# Corsa_LCD.net
KiCad netlist of a schematic drawn in EAGLE
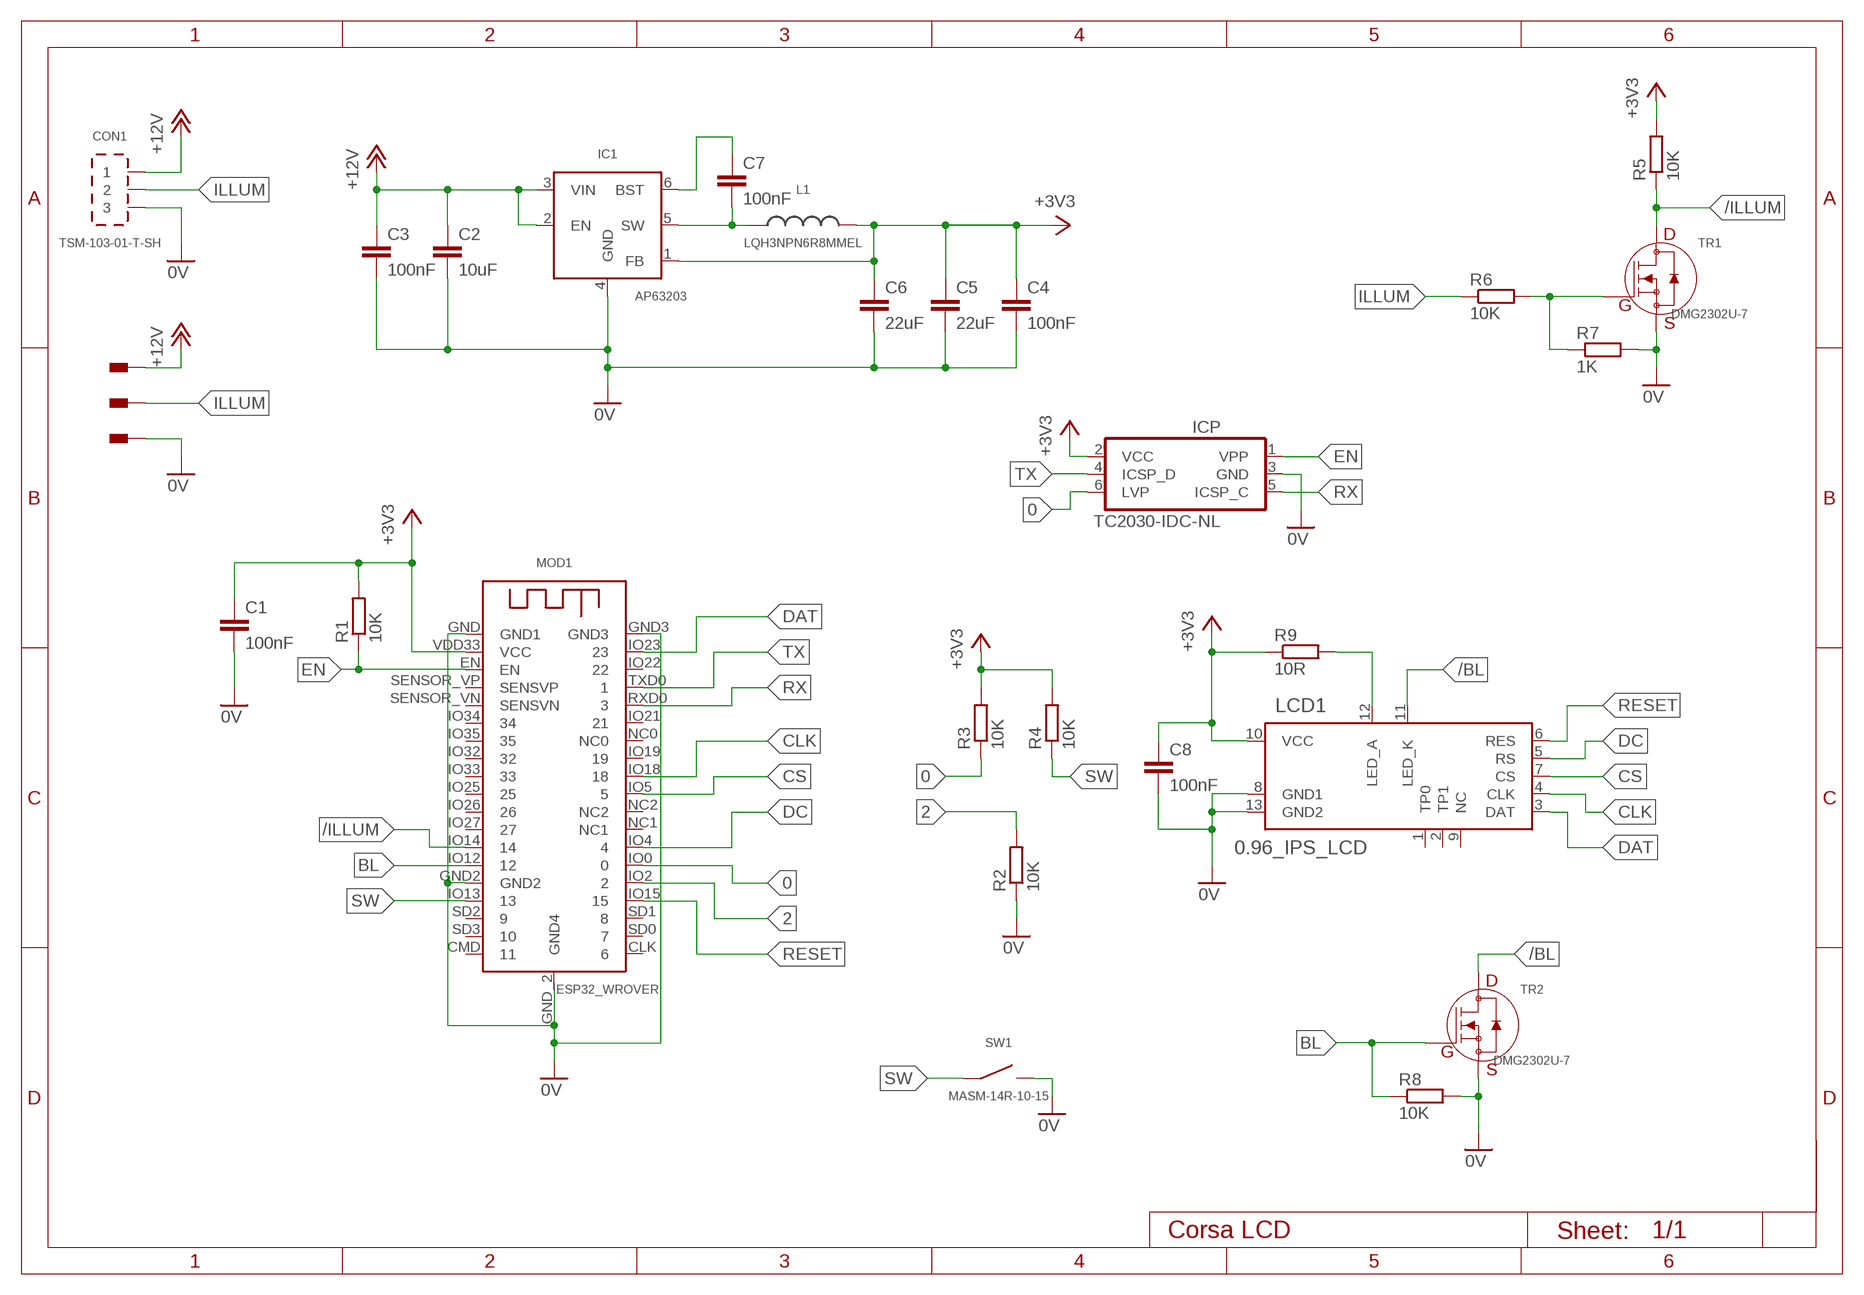
[diagram p0: schematic, sheet 1]

(export (version "E")
  (design (tool "Eeschema 10.0.6"))
  (components
    (comp (ref "C1")
      (value "100nF")
      (footprint "eagle-import:C0603")
      (libsource (lib "eagle-import") (part "C-EUC0603"))
    )
    (comp (ref "C2")
      (value "10uF")
      (footprint "eagle-import:C0603")
      (libsource (lib "eagle-import") (part "C-EUC0603"))
    )
    (comp (ref "C3")
      (value "100nF")
      (footprint "eagle-import:C0603")
      (libsource (lib "eagle-import") (part "C-EUC0603"))
    )
    (comp (ref "C4")
      (value "100nF")
      (footprint "eagle-import:C0603")
      (libsource (lib "eagle-import") (part "C-EUC0603"))
    )
    (comp (ref "C5")
      (value "22uF")
      (footprint "eagle-import:C0603")
      (libsource (lib "eagle-import") (part "C-EUC0603"))
    )
    (comp (ref "C6")
      (value "22uF")
      (footprint "eagle-import:C0603")
      (libsource (lib "eagle-import") (part "C-EUC0603"))
    )
    (comp (ref "C7")
      (value "100nF")
      (footprint "eagle-import:C0603")
      (libsource (lib "eagle-import") (part "C-EUC0603"))
    )
    (comp (ref "C8")
      (value "100nF")
      (footprint "eagle-import:C0603")
      (libsource (lib "eagle-import") (part "C-EUC0603"))
    )
    (comp (ref "CON1")
      (value "TSM-103-01-T-SH")
      (footprint "eagle-import:TSM-103-01-T-SH")
      (libsource (lib "eagle-import") (part "TSM-103-01-T-SH"))
    )
    (comp (ref "IC1")
      (value "AP63203")
      (footprint "eagle-import:TSOT26")
      (libsource (lib "eagle-import") (part "AP63203"))
    )
    (comp (ref "ICP")
      (value "TC2030-IDC-NL")
      (footprint "eagle-import:TC2030-IDC-NL")
      (libsource (lib "eagle-import") (part "TC2030-IDC-NL"))
    )
    (comp (ref "L1")
      (value "LQH3NPN6R8MMEL")
      (footprint "eagle-import:LQH3NPN")
      (libsource (lib "eagle-import") (part "LQH3NPN6R8MMEL"))
    )
    (comp (ref "LCD1")
      (value "0.96_IPS_LCD")
      (footprint "eagle-import:0.96_IPS_LCD")
      (libsource (lib "eagle-import") (part "0.96_IPS_LCD"))
    )
    (comp (ref "MOD1")
      (value "ESP32_WROVER")
      (footprint "eagle-import:ESP32_WROOVER")
      (libsource (lib "eagle-import") (part "ESP32_WROOVER"))
    )
    (comp (ref "PIN1")
      (value "SOLDERPAD")
      (footprint "eagle-import:SOLDERPAD")
      (libsource (lib "eagle-import") (part "SOLDERPAD"))
    )
    (comp (ref "PIN2")
      (value "SOLDERPAD")
      (footprint "eagle-import:SOLDERPAD")
      (libsource (lib "eagle-import") (part "SOLDERPAD"))
    )
    (comp (ref "PIN3")
      (value "SOLDERPAD")
      (footprint "eagle-import:SOLDERPAD")
      (libsource (lib "eagle-import") (part "SOLDERPAD"))
    )
    (comp (ref "R1")
      (value "10K")
      (footprint "eagle-import:R0603")
      (libsource (lib "eagle-import") (part "R-EU_R0603"))
    )
    (comp (ref "R2")
      (value "10K")
      (footprint "eagle-import:R0603")
      (libsource (lib "eagle-import") (part "R-EU_R0603"))
    )
    (comp (ref "R3")
      (value "10K")
      (footprint "eagle-import:R0603")
      (libsource (lib "eagle-import") (part "R-EU_R0603"))
    )
    (comp (ref "R4")
      (value "10K")
      (footprint "eagle-import:R0603")
      (libsource (lib "eagle-import") (part "R-EU_R0603"))
    )
    (comp (ref "R5")
      (value "10K")
      (footprint "eagle-import:R0603")
      (libsource (lib "eagle-import") (part "R-EU_R0603"))
    )
    (comp (ref "R6")
      (value "10K")
      (footprint "eagle-import:R0603")
      (libsource (lib "eagle-import") (part "R-EU_R0603"))
    )
    (comp (ref "R7")
      (value "1K")
      (footprint "eagle-import:R0603")
      (libsource (lib "eagle-import") (part "R-EU_R0603"))
    )
    (comp (ref "R8")
      (value "10K")
      (footprint "eagle-import:R0603")
      (libsource (lib "eagle-import") (part "R-EU_R0603"))
    )
    (comp (ref "R9")
      (value "10R")
      (footprint "eagle-import:R0603")
      (libsource (lib "eagle-import") (part "R-EU_R0603"))
    )
    (comp (ref "SW1")
      (value "MASM-14R-10-15")
      (footprint "eagle-import:MASM-14")
      (libsource (lib "eagle-import") (part "MASM-14R-10-15"))
    )
    (comp (ref "TR1")
      (value "DMG2302U-7")
      (footprint "eagle-import:SOT23")
      (libsource (lib "eagle-import") (part "DMG2302U-7"))
    )
    (comp (ref "TR2")
      (value "DMG2302U-7")
      (footprint "eagle-import:SOT23")
      (libsource (lib "eagle-import") (part "DMG2302U-7"))
    )
  )
  (nets
    (net (code "1") (name "+3V3") (class "Default")
      (node (ref "C1") (pin "1") (pinfunction "1_1") (pintype "passive"))
      (node (ref "C4") (pin "1") (pinfunction "1_1") (pintype "passive"))
      (node (ref "C5") (pin "1") (pinfunction "1_1") (pintype "passive"))
      (node (ref "C6") (pin "1") (pinfunction "1_1") (pintype "passive"))
      (node (ref "C8") (pin "1") (pinfunction "1_1") (pintype "passive"))
      (node (ref "IC1") (pin "1") (pinfunction "FB_1") (pintype "bidirectional"))
      (node (ref "ICP") (pin "2") (pinfunction "VCC_2") (pintype "passive"))
      (node (ref "L1") (pin "2") (pinfunction "2_2") (pintype "bidirectional"))
      (node (ref "LCD1") (pin "10") (pinfunction "VCC_10") (pintype "bidirectional"))
      (node (ref "MOD1") (pin "VDD33") (pinfunction "VCC_VDD33") (pintype "bidirectional"))
      (node (ref "R1") (pin "2") (pinfunction "2_2") (pintype "passive"))
      (node (ref "R3") (pin "2") (pinfunction "2_2") (pintype "passive"))
      (node (ref "R4") (pin "2") (pinfunction "2_2") (pintype "passive"))
      (node (ref "R5") (pin "2") (pinfunction "2_2") (pintype "passive"))
      (node (ref "R9") (pin "1") (pinfunction "1_1") (pintype "passive"))
    )
    (net (code "2") (name "+12V") (class "Default")
      (node (ref "C2") (pin "1") (pinfunction "1_1") (pintype "passive"))
      (node (ref "C3") (pin "1") (pinfunction "1_1") (pintype "passive"))
      (node (ref "CON1") (pin "1") (pinfunction "1_1") (pintype "bidirectional"))
      (node (ref "IC1") (pin "2") (pinfunction "EN_2") (pintype "bidirectional"))
      (node (ref "IC1") (pin "3") (pinfunction "VIN_3") (pintype "bidirectional"))
      (node (ref "PIN1") (pin "1") (pinfunction "1_1") (pintype "bidirectional"))
    )
    (net (code "3") (name "0") (class "Default")
      (node (ref "ICP") (pin "6") (pinfunction "LVP_6") (pintype "passive"))
      (node (ref "MOD1") (pin "IO0") (pinfunction "0_IO0") (pintype "bidirectional"))
      (node (ref "R3") (pin "1") (pinfunction "1_1") (pintype "passive"))
    )
    (net (code "4") (name "0V") (class "Default")
      (node (ref "C1") (pin "2") (pinfunction "2_2") (pintype "passive"))
      (node (ref "C2") (pin "2") (pinfunction "2_2") (pintype "passive"))
      (node (ref "C3") (pin "2") (pinfunction "2_2") (pintype "passive"))
      (node (ref "C4") (pin "2") (pinfunction "2_2") (pintype "passive"))
      (node (ref "C5") (pin "2") (pinfunction "2_2") (pintype "passive"))
      (node (ref "C6") (pin "2") (pinfunction "2_2") (pintype "passive"))
      (node (ref "C8") (pin "2") (pinfunction "2_2") (pintype "passive"))
      (node (ref "CON1") (pin "3") (pinfunction "3_3") (pintype "bidirectional"))
      (node (ref "IC1") (pin "4") (pinfunction "GND_4") (pintype "bidirectional"))
      (node (ref "ICP") (pin "3") (pinfunction "GND_3") (pintype "passive"))
      (node (ref "LCD1") (pin "13") (pinfunction "GND2_13") (pintype "bidirectional"))
      (node (ref "LCD1") (pin "8") (pinfunction "GND1_8") (pintype "bidirectional"))
      (node (ref "MOD1") (pin "GND") (pinfunction "GND1_GND") (pintype "bidirectional"))
      (node (ref "MOD1") (pin "GND2") (pinfunction "GND2_GND2") (pintype "bidirectional"))
      (node (ref "MOD1") (pin "GND3") (pinfunction "GND3_GND3") (pintype "bidirectional"))
      (node (ref "MOD1") (pin "GND_2") (pinfunction "GND4_GND_2") (pintype "bidirectional"))
      (node (ref "PIN3") (pin "1") (pinfunction "1_1") (pintype "bidirectional"))
      (node (ref "R2") (pin "1") (pinfunction "1_1") (pintype "passive"))
      (node (ref "R7") (pin "2") (pinfunction "2_2") (pintype "passive"))
      (node (ref "R8") (pin "2") (pinfunction "2_2") (pintype "passive"))
      (node (ref "SW1") (pin "2") (pinfunction "2_2") (pintype "bidirectional"))
      (node (ref "TR1") (pin "2") (pinfunction "S_2") (pintype "bidirectional"))
      (node (ref "TR2") (pin "2") (pinfunction "S_2") (pintype "bidirectional"))
    )
    (net (code "5") (name "2") (class "Default")
      (node (ref "MOD1") (pin "IO2") (pinfunction "2_IO2") (pintype "bidirectional"))
      (node (ref "R2") (pin "2") (pinfunction "2_2") (pintype "passive"))
    )
    (net (code "6") (name "BL") (class "Default")
      (node (ref "MOD1") (pin "IO12") (pinfunction "12_IO12") (pintype "bidirectional"))
      (node (ref "R8") (pin "1") (pinfunction "1_1") (pintype "passive"))
      (node (ref "TR2") (pin "1") (pinfunction "G_1") (pintype "bidirectional"))
    )
    (net (code "7") (name "CLK") (class "Default")
      (node (ref "LCD1") (pin "4") (pinfunction "CLK_4") (pintype "bidirectional"))
      (node (ref "MOD1") (pin "IO18") (pinfunction "18_IO18") (pintype "bidirectional"))
    )
    (net (code "8") (name "CS") (class "Default")
      (node (ref "LCD1") (pin "7") (pinfunction "CS_7") (pintype "bidirectional"))
      (node (ref "MOD1") (pin "IO5") (pinfunction "5_IO5") (pintype "bidirectional"))
    )
    (net (code "9") (name "DAT") (class "Default")
      (node (ref "LCD1") (pin "3") (pinfunction "DAT_3") (pintype "bidirectional"))
      (node (ref "MOD1") (pin "IO23") (pinfunction "23_IO23") (pintype "bidirectional"))
    )
    (net (code "10") (name "DC") (class "Default")
      (node (ref "LCD1") (pin "5") (pinfunction "RS_5") (pintype "bidirectional"))
      (node (ref "MOD1") (pin "IO4") (pinfunction "4_IO4") (pintype "bidirectional"))
    )
    (net (code "11") (name "EN") (class "Default")
      (node (ref "ICP") (pin "1") (pinfunction "VPP_1") (pintype "passive"))
      (node (ref "MOD1") (pin "EN") (pinfunction "EN_EN") (pintype "bidirectional"))
      (node (ref "R1") (pin "1") (pinfunction "1_1") (pintype "passive"))
    )
    (net (code "12") (name "ILLUM") (class "Default")
      (node (ref "CON1") (pin "2") (pinfunction "2_2") (pintype "bidirectional"))
      (node (ref "PIN2") (pin "1") (pinfunction "1_1") (pintype "bidirectional"))
      (node (ref "R6") (pin "1") (pinfunction "1_1") (pintype "passive"))
    )
    (net (code "13") (name "Net-(IC1-BST)") (class "Default")
      (node (ref "C7") (pin "1") (pinfunction "1_1") (pintype "passive"))
      (node (ref "IC1") (pin "6") (pinfunction "BST_6") (pintype "bidirectional"))
    )
    (net (code "14") (name "Net-(IC1-SW)") (class "Default")
      (node (ref "C7") (pin "2") (pinfunction "2_2") (pintype "passive"))
      (node (ref "IC1") (pin "5") (pinfunction "SW_5") (pintype "bidirectional"))
      (node (ref "L1") (pin "1") (pinfunction "1_1") (pintype "bidirectional"))
    )
    (net (code "15") (name "Net-(LCD1-LED_A)") (class "Default")
      (node (ref "LCD1") (pin "12") (pinfunction "LED_A_12") (pintype "bidirectional"))
      (node (ref "R9") (pin "2") (pinfunction "2_2") (pintype "passive"))
    )
    (net (code "16") (name "Net-(TR1-G)") (class "Default")
      (node (ref "R6") (pin "2") (pinfunction "2_2") (pintype "passive"))
      (node (ref "R7") (pin "1") (pinfunction "1_1") (pintype "passive"))
      (node (ref "TR1") (pin "1") (pinfunction "G_1") (pintype "bidirectional"))
    )
    (net (code "17") (name "RESET") (class "Default")
      (node (ref "LCD1") (pin "6") (pinfunction "RES_6") (pintype "bidirectional"))
      (node (ref "MOD1") (pin "IO15") (pinfunction "15_IO15") (pintype "bidirectional"))
    )
    (net (code "18") (name "RX") (class "Default")
      (node (ref "ICP") (pin "5") (pinfunction "ICSP_C_5") (pintype "passive"))
      (node (ref "MOD1") (pin "RXD0") (pinfunction "3_RXD0") (pintype "bidirectional"))
    )
    (net (code "19") (name "SW") (class "Default")
      (node (ref "MOD1") (pin "IO13") (pinfunction "13_IO13") (pintype "bidirectional"))
      (node (ref "R4") (pin "1") (pinfunction "1_1") (pintype "passive"))
      (node (ref "SW1") (pin "1") (pinfunction "1_1") (pintype "bidirectional"))
    )
    (net (code "20") (name "TX") (class "Default")
      (node (ref "ICP") (pin "4") (pinfunction "ICSP_D_4") (pintype "passive"))
      (node (ref "MOD1") (pin "TXD0") (pinfunction "1_TXD0") (pintype "bidirectional"))
    )
    (net (code "21") (name "unconnected-(LCD1-NC-Pad9)") (class "Default")
      (node (ref "LCD1") (pin "9") (pinfunction "NC_9") (pintype "bidirectional"))
    )
    (net (code "22") (name "unconnected-(LCD1-TP0-Pad1)") (class "Default")
      (node (ref "LCD1") (pin "1") (pinfunction "TP0_1") (pintype "bidirectional"))
    )
    (net (code "23") (name "unconnected-(LCD1-TP1-Pad2)") (class "Default")
      (node (ref "LCD1") (pin "2") (pinfunction "TP1_2") (pintype "bidirectional"))
    )
    (net (code "24") (name "unconnected-(MOD1-6-PadCLK)") (class "Default")
      (node (ref "MOD1") (pin "CLK") (pinfunction "6_CLK") (pintype "bidirectional"))
    )
    (net (code "25") (name "unconnected-(MOD1-7-PadSD0)") (class "Default")
      (node (ref "MOD1") (pin "SD0") (pinfunction "7_SD0") (pintype "bidirectional"))
    )
    (net (code "26") (name "unconnected-(MOD1-8-PadSD1)") (class "Default")
      (node (ref "MOD1") (pin "SD1") (pinfunction "8_SD1") (pintype "bidirectional"))
    )
    (net (code "27") (name "unconnected-(MOD1-9-PadSD2)") (class "Default")
      (node (ref "MOD1") (pin "SD2") (pinfunction "9_SD2") (pintype "bidirectional"))
    )
    (net (code "28") (name "unconnected-(MOD1-10-PadSD3)") (class "Default")
      (node (ref "MOD1") (pin "SD3") (pinfunction "10_SD3") (pintype "bidirectional"))
    )
    (net (code "29") (name "unconnected-(MOD1-11-PadCMD)") (class "Default")
      (node (ref "MOD1") (pin "CMD") (pinfunction "11_CMD") (pintype "bidirectional"))
    )
    (net (code "30") (name "unconnected-(MOD1-19-PadIO19)") (class "Default")
      (node (ref "MOD1") (pin "IO19") (pinfunction "19_IO19") (pintype "bidirectional"))
    )
    (net (code "31") (name "unconnected-(MOD1-21-PadIO21)") (class "Default")
      (node (ref "MOD1") (pin "IO21") (pinfunction "21_IO21") (pintype "bidirectional"))
    )
    (net (code "32") (name "unconnected-(MOD1-22-PadIO22)") (class "Default")
      (node (ref "MOD1") (pin "IO22") (pinfunction "22_IO22") (pintype "bidirectional"))
    )
    (net (code "33") (name "unconnected-(MOD1-25-PadIO25)") (class "Default")
      (node (ref "MOD1") (pin "IO25") (pinfunction "25_IO25") (pintype "bidirectional"))
    )
    (net (code "34") (name "unconnected-(MOD1-26-PadIO26)") (class "Default")
      (node (ref "MOD1") (pin "IO26") (pinfunction "26_IO26") (pintype "bidirectional"))
    )
    (net (code "35") (name "unconnected-(MOD1-27-PadIO27)") (class "Default")
      (node (ref "MOD1") (pin "IO27") (pinfunction "27_IO27") (pintype "bidirectional"))
    )
    (net (code "36") (name "unconnected-(MOD1-32-PadIO32)") (class "Default")
      (node (ref "MOD1") (pin "IO32") (pinfunction "32_IO32") (pintype "bidirectional"))
    )
    (net (code "37") (name "unconnected-(MOD1-33-PadIO33)") (class "Default")
      (node (ref "MOD1") (pin "IO33") (pinfunction "33_IO33") (pintype "bidirectional"))
    )
    (net (code "38") (name "unconnected-(MOD1-34-PadIO34)") (class "Default")
      (node (ref "MOD1") (pin "IO34") (pinfunction "34_IO34") (pintype "bidirectional"))
    )
    (net (code "39") (name "unconnected-(MOD1-35-PadIO35)") (class "Default")
      (node (ref "MOD1") (pin "IO35") (pinfunction "35_IO35") (pintype "bidirectional"))
    )
    (net (code "40") (name "unconnected-(MOD1-PadNC0)") (class "Default")
      (node (ref "MOD1") (pin "NC0") (pinfunction "NC0_NC0") (pintype "bidirectional"))
    )
    (net (code "41") (name "unconnected-(MOD1-PadNC1)") (class "Default")
      (node (ref "MOD1") (pin "NC1") (pinfunction "NC1_NC1") (pintype "bidirectional"))
    )
    (net (code "42") (name "unconnected-(MOD1-PadNC2)") (class "Default")
      (node (ref "MOD1") (pin "NC2") (pinfunction "NC2_NC2") (pintype "bidirectional"))
    )
    (net (code "43") (name "unconnected-(MOD1-SENSVN-PadSENSOR_VN)") (class "Default")
      (node (ref "MOD1") (pin "SENSOR_VN") (pinfunction "SENSVN_SENSOR_VN") (pintype "bidirectional"))
    )
    (net (code "44") (name "unconnected-(MOD1-SENSVP-PadSENSOR_VP)") (class "Default")
      (node (ref "MOD1") (pin "SENSOR_VP") (pinfunction "SENSVP_SENSOR_VP") (pintype "bidirectional"))
    )
    (net (code "45") (name "{slash}BL") (class "Default")
      (node (ref "LCD1") (pin "11") (pinfunction "LED_K_11") (pintype "bidirectional"))
      (node (ref "TR2") (pin "3") (pinfunction "D_3") (pintype "bidirectional"))
    )
    (net (code "46") (name "{slash}ILLUM") (class "Default")
      (node (ref "MOD1") (pin "IO14") (pinfunction "14_IO14") (pintype "bidirectional"))
      (node (ref "R5") (pin "1") (pinfunction "1_1") (pintype "passive"))
      (node (ref "TR1") (pin "3") (pinfunction "D_3") (pintype "bidirectional"))
    )
  )
)
